# LipSync4_Main_Board_Alpha2.net
KiCad netlist of a schematic drawn in EAGLE
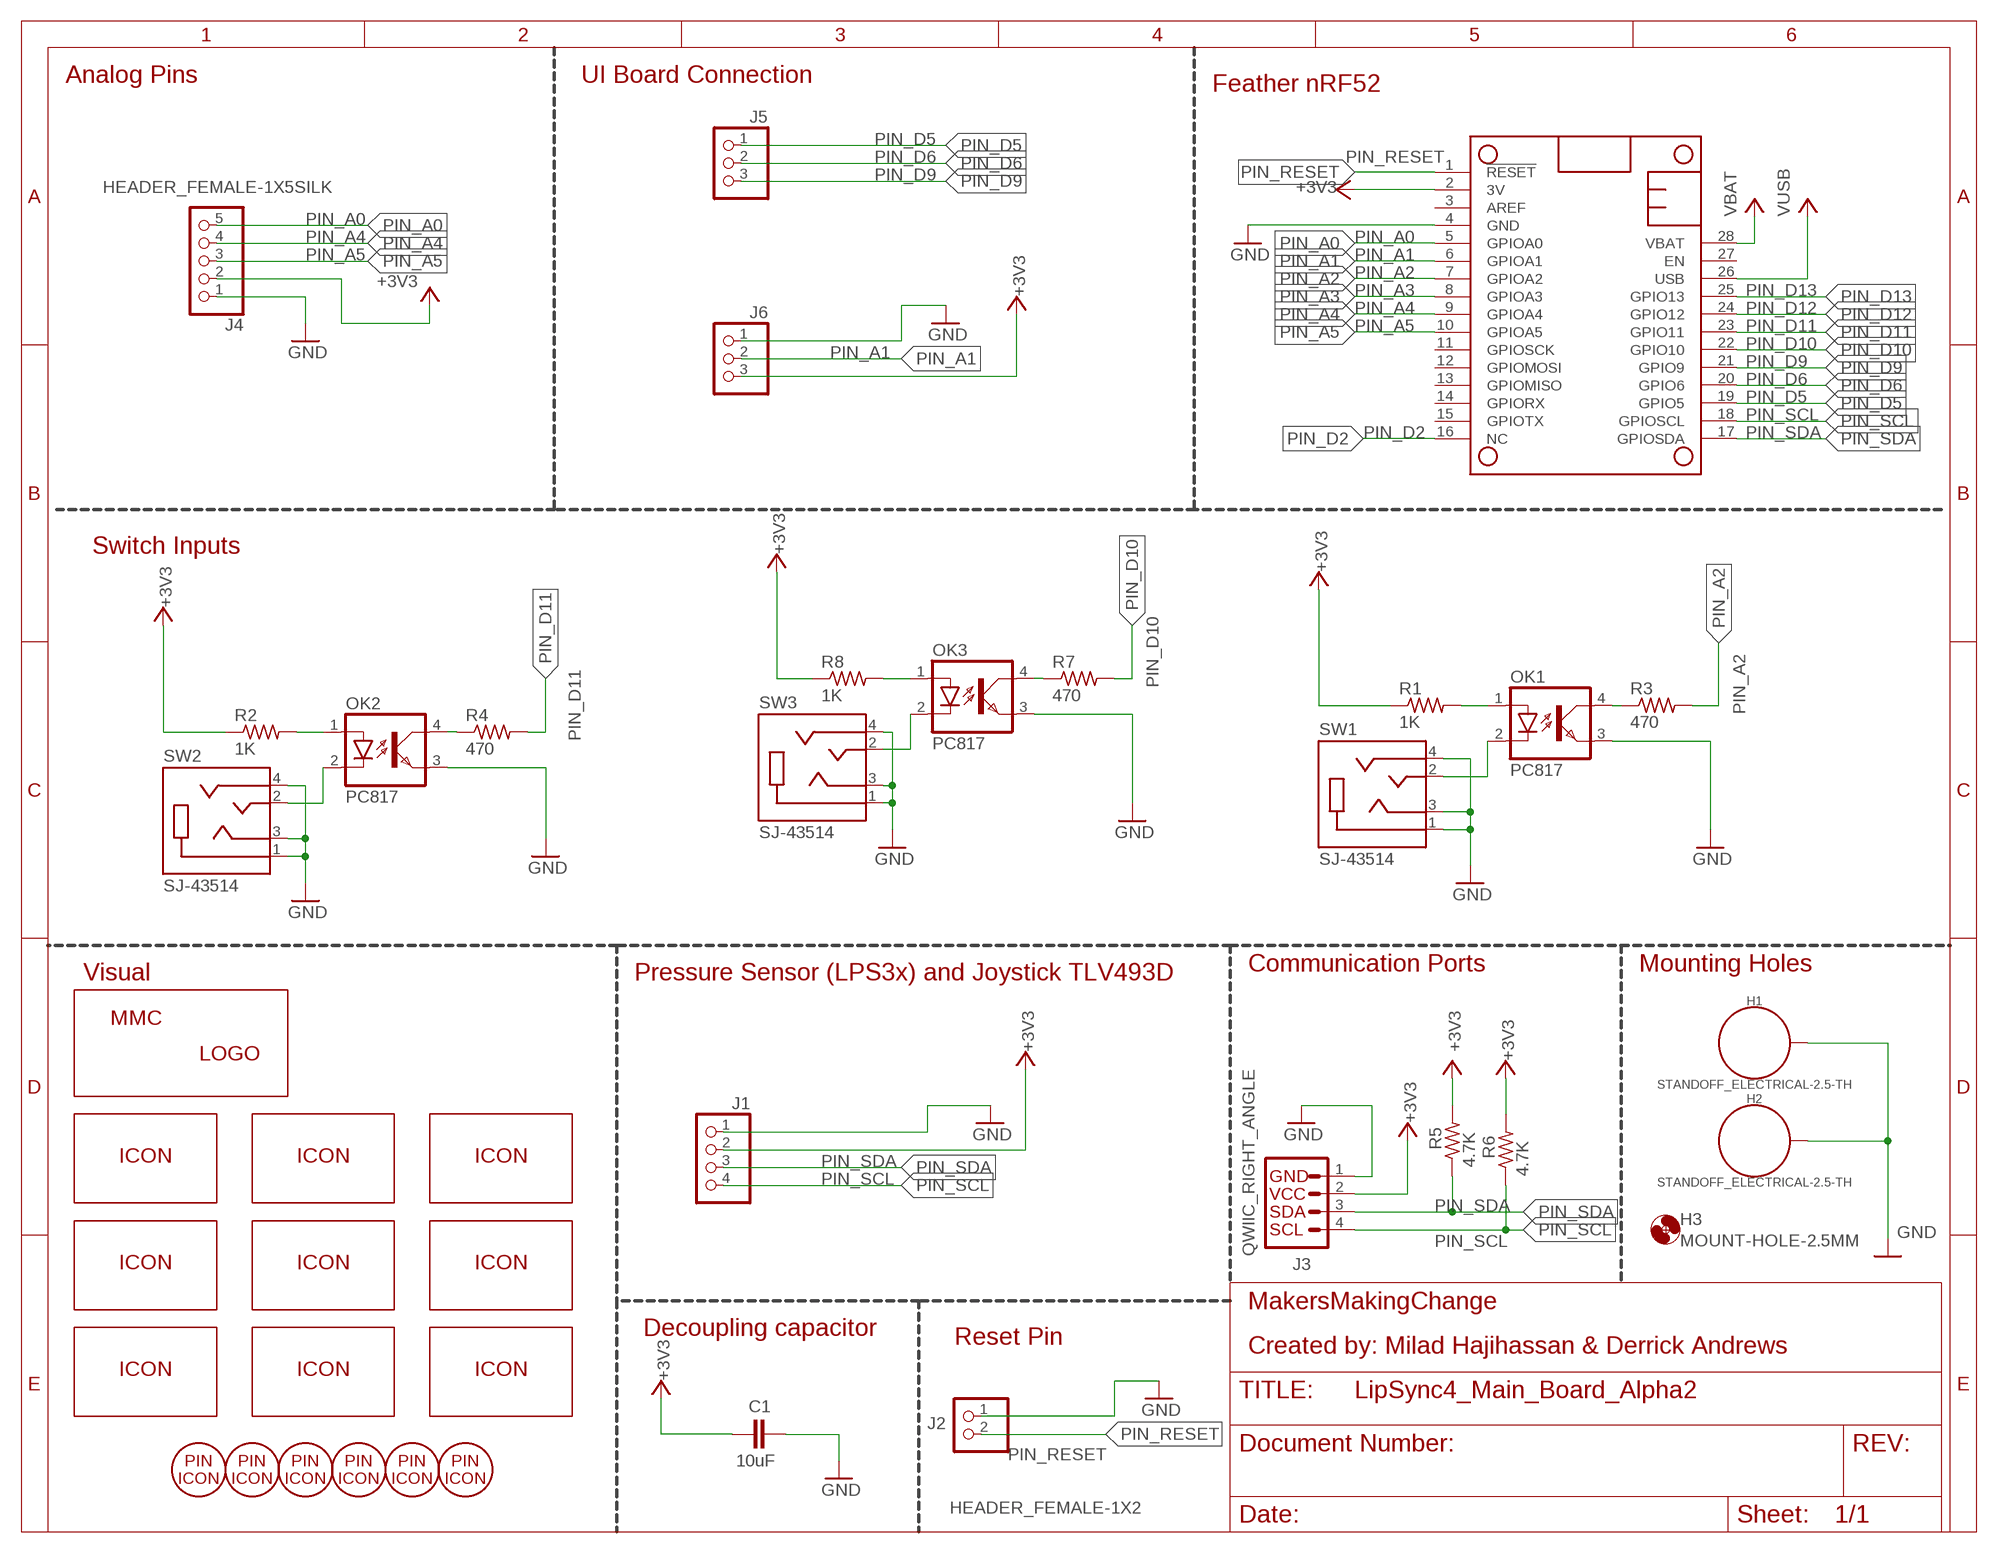
[diagram p0: schematic, sheet 1]

(export (version "E")
  (design (tool "Eeschema 10.0.6"))
  (components
    (comp (ref "C1")
      (value "10uF")
      (footprint "eagle-import:CAP-025-025X040")
      (libsource (lib "eagle-import") (part "CAPACITOR-025-025X040"))
    )
    (comp (ref "H1")
      (value "STANDOFF_ELECTRICAL-2.5-TH")
      (footprint "eagle-import:STANDOFF-ELECTRICAL-2.5-TH")
      (libsource (lib "eagle-import") (part "STANDOFF_ELECTRICAL-2.5-TH"))
    )
    (comp (ref "H2")
      (value "STANDOFF_ELECTRICAL-2.5-TH")
      (footprint "eagle-import:STANDOFF-ELECTRICAL-2.5-TH")
      (libsource (lib "eagle-import") (part "STANDOFF_ELECTRICAL-2.5-TH"))
    )
    (comp (ref "H3")
      (value "MOUNT-HOLE-2.5MM")
      (footprint "eagle-import:HOLE-2.5MM")
      (libsource (lib "eagle-import") (part "MOUNT-HOLE-2.5MM"))
    )
    (comp (ref "J1")
      (value "HEADER_FEMALE-1X4")
      (footprint "eagle-import:HEADER_FEMALE-1X04")
      (libsource (lib "eagle-import") (part "HEADER_FEMALE-1X4"))
    )
    (comp (ref "J2")
      (value "HEADER_FEMALE-1X2")
      (footprint "eagle-import:HEADER_FEMALE-1X02")
      (libsource (lib "eagle-import") (part "HEADER_FEMALE-1X2"))
    )
    (comp (ref "J3")
      (value "QWIIC_RIGHT_ANGLE")
      (footprint "eagle-import:CONNECTORS_JST04_1MM_RA")
      (libsource (lib "eagle-import") (part "QWIIC_CONNECTORSJS-1MM"))
    )
    (comp (ref "J4")
      (value "HEADER_FEMALE-1X5SILK")
      (footprint "eagle-import:HEADER_FEMALE-1X05_SILK")
      (libsource (lib "eagle-import") (part "HEADER_FEMALE-1X5SILK"))
    )
    (comp (ref "J5")
      (value "HEADER_MALE-1X03/270")
      (footprint "eagle-import:HEADER_MALE-1X03_LOCK_270")
      (libsource (lib "eagle-import") (part "HEADER_MALE-1X03/270"))
    )
    (comp (ref "J6")
      (value "HEADER_MALE-1X03/270")
      (footprint "eagle-import:HEADER_MALE-1X03_LOCK_270")
      (libsource (lib "eagle-import") (part "HEADER_MALE-1X03/270"))
    )
    (comp (ref "LABEL_ALPHA2")
      (value "MMC_ICON-ALPHA2")
      (footprint "eagle-import:ICON_ALPHA2")
      (libsource (lib "eagle-import") (part "MMC_ICON-ALPHA2"))
    )
    (comp (ref "LABEL_I2C")
      (value "MMC_ICON-I2C")
      (footprint "eagle-import:ICON_I2C")
      (libsource (lib "eagle-import") (part "MMC_ICON-I2C"))
    )
    (comp (ref "LABEL_ICON_PIN-DATA")
      (value "MMC_PIN-ICON-DATA")
      (footprint "eagle-import:PIN-ICON_DATA")
      (libsource (lib "eagle-import") (part "MMC_PIN-ICON-DATA"))
    )
    (comp (ref "LABEL_ICON_PIN-GND")
      (value "MMC_PIN-ICON-GND")
      (footprint "eagle-import:PIN-ICON_GND")
      (libsource (lib "eagle-import") (part "MMC_PIN-ICON-GND"))
    )
    (comp (ref "LABEL_ICON_PIN-VCC")
      (value "MMC_PIN-ICON-VCC")
      (footprint "eagle-import:PIN-ICON_VCC")
      (libsource (lib "eagle-import") (part "MMC_PIN-ICON-VCC"))
    )
    (comp (ref "LABEL_ICON_PIN1")
      (value "MMC_PIN-ICON-PIN1")
      (footprint "eagle-import:PIN-ICON_1")
      (libsource (lib "eagle-import") (part "MMC_PIN-ICON-PIN1"))
    )
    (comp (ref "LABEL_ICON_PIN2")
      (value "MMC_PIN-ICON-PIN2")
      (footprint "eagle-import:PIN-ICON_2")
      (libsource (lib "eagle-import") (part "MMC_PIN-ICON-PIN2"))
    )
    (comp (ref "LABEL_ICON_PIN3")
      (value "MMC_PIN-ICON-PIN3")
      (footprint "eagle-import:PIN-ICON_3")
      (libsource (lib "eagle-import") (part "MMC_PIN-ICON-PIN3"))
    )
    (comp (ref "LABEL_LIPSYNC4")
      (value "MMC_ICON-LIPSYNC4")
      (footprint "eagle-import:ICON_LIPSYNC4")
      (libsource (lib "eagle-import") (part "MMC_ICON-LIPSYNC4"))
    )
    (comp (ref "LABEL_MAIN-BOARD")
      (value "MMC_ICON-MAIN-BOARD")
      (footprint "eagle-import:ICON_MAIN-BOARD")
      (libsource (lib "eagle-import") (part "MMC_ICON-MAIN-BOARD"))
    )
    (comp (ref "LABEL_MMC")
      (value "MMC_LOGO-SM")
      (footprint "eagle-import:MMC_SMALL_LOGO")
      (libsource (lib "eagle-import") (part "MMC_LOGO-SM"))
    )
    (comp (ref "LABEL_RESET")
      (value "MMC_ICON-RESET")
      (footprint "eagle-import:ICON_RESET")
      (libsource (lib "eagle-import") (part "MMC_ICON-RESET"))
    )
    (comp (ref "LABEL_SPEAKER")
      (value "MMC_ICON-SPEAKER")
      (footprint "eagle-import:ICON_SPEAKER")
      (libsource (lib "eagle-import") (part "MMC_ICON-SPEAKER"))
    )
    (comp (ref "LABEL_STEMMA")
      (value "MMC_ICON-STEMMA")
      (footprint "eagle-import:ICON_STEMMA")
      (libsource (lib "eagle-import") (part "MMC_ICON-STEMMA"))
    )
    (comp (ref "LABE_BUTTON")
      (value "MMC_ICON-BUTTON")
      (footprint "eagle-import:ICON_BUTTON")
      (libsource (lib "eagle-import") (part "MMC_ICON-BUTTON"))
    )
    (comp (ref "LABE_LED")
      (value "MMC_ICON-LED")
      (footprint "eagle-import:ICON_LED")
      (libsource (lib "eagle-import") (part "MMC_ICON-LED"))
    )
    (comp (ref "OK1")
      (value "PC817")
      (footprint "eagle-import:DIL04")
      (libsource (lib "eagle-import") (part "PC817"))
    )
    (comp (ref "OK2")
      (value "PC817")
      (footprint "eagle-import:DIL04")
      (libsource (lib "eagle-import") (part "PC817"))
    )
    (comp (ref "OK3")
      (value "PC817")
      (footprint "eagle-import:DIL04")
      (libsource (lib "eagle-import") (part "PC817"))
    )
    (comp (ref "R1")
      (value "1K")
      (footprint "eagle-import:RESISTOR_0204_5")
      (libsource (lib "eagle-import") (part "RESISTOR-US-0204/5"))
    )
    (comp (ref "R2")
      (value "1K")
      (footprint "eagle-import:RESISTOR_0204_5")
      (libsource (lib "eagle-import") (part "RESISTOR-US-0204/5"))
    )
    (comp (ref "R3")
      (value "470")
      (footprint "eagle-import:RESISTOR_0204_5")
      (libsource (lib "eagle-import") (part "RESISTOR-US-0204/5"))
    )
    (comp (ref "R4")
      (value "470")
      (footprint "eagle-import:RESISTOR_0204_5")
      (libsource (lib "eagle-import") (part "RESISTOR-US-0204/5"))
    )
    (comp (ref "R5")
      (value "4.7K")
      (footprint "eagle-import:RESISTOR_0204_5")
      (libsource (lib "eagle-import") (part "RESISTOR-US-0204/5"))
    )
    (comp (ref "R6")
      (value "4.7K")
      (footprint "eagle-import:RESISTOR_0204_5")
      (libsource (lib "eagle-import") (part "RESISTOR-US-0204/5"))
    )
    (comp (ref "R7")
      (value "470")
      (footprint "eagle-import:RESISTOR_0204_5")
      (libsource (lib "eagle-import") (part "RESISTOR-US-0204/5"))
    )
    (comp (ref "R8")
      (value "1K")
      (footprint "eagle-import:RESISTOR_0204_5")
      (libsource (lib "eagle-import") (part "RESISTOR-US-0204/5"))
    )
    (comp (ref "SW1")
      (value "SJ-43514")
      (footprint "eagle-import:CUI_SJ-43514")
      (libsource (lib "eagle-import") (part "SJ-43514"))
    )
    (comp (ref "SW2")
      (value "SJ-43514")
      (footprint "eagle-import:CUI_SJ-43514")
      (libsource (lib "eagle-import") (part "SJ-43514"))
    )
    (comp (ref "SW3")
      (value "SJ-43514")
      (footprint "eagle-import:CUI_SJ-43514")
      (libsource (lib "eagle-import") (part "SJ-43514"))
    )
    (comp (ref "U1")
      (value "ADAFRUIT_FEATHER_NODIM")
      (footprint "eagle-import:ADAFRUIT_FEATHERWING_DIM")
      (libsource (lib "eagle-import") (part "ADAFRUIT_FEATHER_NODIM"))
    )
  )
  (nets
    (net (code "1") (name "+3V3") (class "Default")
      (node (ref "C1") (pin "2") (pinfunction "2_2") (pintype "passive"))
      (node (ref "J1") (pin "2") (pinfunction "2_2") (pintype "passive"))
      (node (ref "J3") (pin "2") (pinfunction "2_2") (pintype "power_in"))
      (node (ref "J4") (pin "2") (pinfunction "2_2") (pintype "passive"))
      (node (ref "J6") (pin "3") (pinfunction "3_3") (pintype "passive"))
      (node (ref "R1") (pin "1") (pinfunction "1_1") (pintype "passive"))
      (node (ref "R2") (pin "1") (pinfunction "1_1") (pintype "passive"))
      (node (ref "R5") (pin "2") (pinfunction "2_2") (pintype "passive"))
      (node (ref "R6") (pin "2") (pinfunction "2_2") (pintype "passive"))
      (node (ref "R8") (pin "1") (pinfunction "1_1") (pintype "passive"))
      (node (ref "U1") (pin "2") (pinfunction "3V_2") (pintype "power_in"))
    )
    (net (code "2") (name "GND") (class "Default")
      (node (ref "C1") (pin "1") (pinfunction "1_1") (pintype "passive"))
      (node (ref "H1") (pin "P1") (pinfunction "P$1_P1") (pintype "bidirectional"))
      (node (ref "H2") (pin "P1") (pinfunction "P$1_P1") (pintype "bidirectional"))
      (node (ref "J1") (pin "1") (pinfunction "1_1") (pintype "passive"))
      (node (ref "J2") (pin "1") (pinfunction "1_1") (pintype "passive"))
      (node (ref "J3") (pin "1") (pinfunction "1_1") (pintype "power_in"))
      (node (ref "J4") (pin "1") (pinfunction "1_1") (pintype "passive"))
      (node (ref "J6") (pin "1") (pinfunction "1_1") (pintype "passive"))
      (node (ref "OK1") (pin "3") (pinfunction "EMIT_3") (pintype "passive"))
      (node (ref "OK2") (pin "3") (pinfunction "EMIT_3") (pintype "passive"))
      (node (ref "OK3") (pin "3") (pinfunction "EMIT_3") (pintype "passive"))
      (node (ref "SW1") (pin "1") (pinfunction "SLEEVE_1") (pintype "passive"))
      (node (ref "SW1") (pin "3") (pinfunction "RING1_3") (pintype "passive"))
      (node (ref "SW1") (pin "4") (pinfunction "RING2_4") (pintype "passive"))
      (node (ref "SW2") (pin "1") (pinfunction "SLEEVE_1") (pintype "passive"))
      (node (ref "SW2") (pin "3") (pinfunction "RING1_3") (pintype "passive"))
      (node (ref "SW2") (pin "4") (pinfunction "RING2_4") (pintype "passive"))
      (node (ref "SW3") (pin "1") (pinfunction "SLEEVE_1") (pintype "passive"))
      (node (ref "SW3") (pin "3") (pinfunction "RING1_3") (pintype "passive"))
      (node (ref "SW3") (pin "4") (pinfunction "RING2_4") (pintype "passive"))
      (node (ref "U1") (pin "4") (pinfunction "GND_4") (pintype "power_in"))
    )
    (net (code "3") (name "Net-(OK1-A)") (class "Default")
      (node (ref "OK1") (pin "1") (pinfunction "A_1") (pintype "passive"))
      (node (ref "R1") (pin "2") (pinfunction "2_2") (pintype "passive"))
    )
    (net (code "4") (name "Net-(OK1-C)") (class "Default")
      (node (ref "OK1") (pin "2") (pinfunction "C_2") (pintype "passive"))
      (node (ref "SW1") (pin "2") (pinfunction "TIP_2") (pintype "passive"))
    )
    (net (code "5") (name "Net-(OK1-COL)") (class "Default")
      (node (ref "OK1") (pin "4") (pinfunction "COL_4") (pintype "passive"))
      (node (ref "R3") (pin "1") (pinfunction "1_1") (pintype "passive"))
    )
    (net (code "6") (name "Net-(OK2-A)") (class "Default")
      (node (ref "OK2") (pin "1") (pinfunction "A_1") (pintype "passive"))
      (node (ref "R2") (pin "2") (pinfunction "2_2") (pintype "passive"))
    )
    (net (code "7") (name "Net-(OK2-C)") (class "Default")
      (node (ref "OK2") (pin "2") (pinfunction "C_2") (pintype "passive"))
      (node (ref "SW2") (pin "2") (pinfunction "TIP_2") (pintype "passive"))
    )
    (net (code "8") (name "Net-(OK2-COL)") (class "Default")
      (node (ref "OK2") (pin "4") (pinfunction "COL_4") (pintype "passive"))
      (node (ref "R4") (pin "1") (pinfunction "1_1") (pintype "passive"))
    )
    (net (code "9") (name "Net-(OK3-A)") (class "Default")
      (node (ref "OK3") (pin "1") (pinfunction "A_1") (pintype "passive"))
      (node (ref "R8") (pin "2") (pinfunction "2_2") (pintype "passive"))
    )
    (net (code "10") (name "Net-(OK3-C)") (class "Default")
      (node (ref "OK3") (pin "2") (pinfunction "C_2") (pintype "passive"))
      (node (ref "SW3") (pin "2") (pinfunction "TIP_2") (pintype "passive"))
    )
    (net (code "11") (name "Net-(OK3-COL)") (class "Default")
      (node (ref "OK3") (pin "4") (pinfunction "COL_4") (pintype "passive"))
      (node (ref "R7") (pin "1") (pinfunction "1_1") (pintype "passive"))
    )
    (net (code "12") (name "PIN_A0") (class "Default")
      (node (ref "J4") (pin "5") (pinfunction "5_5") (pintype "passive"))
      (node (ref "U1") (pin "5") (pinfunction "GPIOA0_5") (pintype "bidirectional"))
    )
    (net (code "13") (name "PIN_A1") (class "Default")
      (node (ref "J6") (pin "2") (pinfunction "2_2") (pintype "passive"))
      (node (ref "U1") (pin "6") (pinfunction "GPIOA1_6") (pintype "bidirectional"))
    )
    (net (code "14") (name "PIN_A2") (class "Default")
      (node (ref "R3") (pin "2") (pinfunction "2_2") (pintype "passive"))
      (node (ref "U1") (pin "7") (pinfunction "GPIOA2_7") (pintype "bidirectional"))
    )
    (net (code "15") (name "PIN_A3") (class "Default")
      (node (ref "U1") (pin "8") (pinfunction "GPIOA3_8") (pintype "bidirectional"))
    )
    (net (code "16") (name "PIN_A4") (class "Default")
      (node (ref "J4") (pin "4") (pinfunction "4_4") (pintype "passive"))
      (node (ref "U1") (pin "9") (pinfunction "GPIOA4_9") (pintype "bidirectional"))
    )
    (net (code "17") (name "PIN_A5") (class "Default")
      (node (ref "J4") (pin "3") (pinfunction "3_3") (pintype "passive"))
      (node (ref "U1") (pin "10") (pinfunction "GPIOA5_10") (pintype "bidirectional"))
    )
    (net (code "18") (name "PIN_D2") (class "Default")
      (node (ref "U1") (pin "16") (pinfunction "NC_16") (pintype "passive"))
    )
    (net (code "19") (name "PIN_D5") (class "Default")
      (node (ref "J5") (pin "1") (pinfunction "1_1") (pintype "passive"))
      (node (ref "U1") (pin "19") (pinfunction "GPIO5_19") (pintype "bidirectional"))
    )
    (net (code "20") (name "PIN_D6") (class "Default")
      (node (ref "J5") (pin "2") (pinfunction "2_2") (pintype "passive"))
      (node (ref "U1") (pin "20") (pinfunction "GPIO6_20") (pintype "bidirectional"))
    )
    (net (code "21") (name "PIN_D9") (class "Default")
      (node (ref "J5") (pin "3") (pinfunction "3_3") (pintype "passive"))
      (node (ref "U1") (pin "21") (pinfunction "GPIO9_21") (pintype "bidirectional"))
    )
    (net (code "22") (name "PIN_D10") (class "Default")
      (node (ref "R7") (pin "2") (pinfunction "2_2") (pintype "passive"))
      (node (ref "U1") (pin "22") (pinfunction "GPIO10_22") (pintype "bidirectional"))
    )
    (net (code "23") (name "PIN_D11") (class "Default")
      (node (ref "R4") (pin "2") (pinfunction "2_2") (pintype "passive"))
      (node (ref "U1") (pin "23") (pinfunction "GPIO11_23") (pintype "bidirectional"))
    )
    (net (code "24") (name "PIN_D12") (class "Default")
      (node (ref "U1") (pin "24") (pinfunction "GPIO12_24") (pintype "bidirectional"))
    )
    (net (code "25") (name "PIN_D13") (class "Default")
      (node (ref "U1") (pin "25") (pinfunction "GPIO13_25") (pintype "bidirectional"))
    )
    (net (code "26") (name "PIN_RESET") (class "Default")
      (node (ref "J2") (pin "2") (pinfunction "2_2") (pintype "passive"))
      (node (ref "U1") (pin "1") (pinfunction "~{RESET}_1") (pintype "input"))
    )
    (net (code "27") (name "PIN_SCL") (class "Default")
      (node (ref "J1") (pin "4") (pinfunction "4_4") (pintype "passive"))
      (node (ref "J3") (pin "4") (pinfunction "4_4") (pintype "passive"))
      (node (ref "R6") (pin "1") (pinfunction "1_1") (pintype "passive"))
      (node (ref "U1") (pin "18") (pinfunction "GPIOSCL_18") (pintype "bidirectional"))
    )
    (net (code "28") (name "PIN_SDA") (class "Default")
      (node (ref "J1") (pin "3") (pinfunction "3_3") (pintype "passive"))
      (node (ref "J3") (pin "3") (pinfunction "3_3") (pintype "passive"))
      (node (ref "R5") (pin "1") (pinfunction "1_1") (pintype "passive"))
      (node (ref "U1") (pin "17") (pinfunction "GPIOSDA_17") (pintype "bidirectional"))
    )
    (net (code "29") (name "VBAT") (class "Default")
      (node (ref "U1") (pin "28") (pinfunction "VBAT_28") (pintype "power_in"))
    )
    (net (code "30") (name "VUSB") (class "Default")
      (node (ref "U1") (pin "26") (pinfunction "USB_26") (pintype "power_in"))
    )
    (net (code "31") (name "unconnected-(U1-AREF-Pad3)") (class "Default")
      (node (ref "U1") (pin "3") (pinfunction "AREF_3") (pintype "passive"))
    )
    (net (code "32") (name "unconnected-(U1-EN-Pad27)") (class "Default")
      (node (ref "U1") (pin "27") (pinfunction "EN_27") (pintype "passive"))
    )
    (net (code "33") (name "unconnected-(U1-GPIOMISO-Pad13)") (class "Default")
      (node (ref "U1") (pin "13") (pinfunction "GPIOMISO_13") (pintype "bidirectional"))
    )
    (net (code "34") (name "unconnected-(U1-GPIOMOSI-Pad12)") (class "Default")
      (node (ref "U1") (pin "12") (pinfunction "GPIOMOSI_12") (pintype "bidirectional"))
    )
    (net (code "35") (name "unconnected-(U1-GPIORX-Pad14)") (class "Default")
      (node (ref "U1") (pin "14") (pinfunction "GPIORX_14") (pintype "bidirectional"))
    )
    (net (code "36") (name "unconnected-(U1-GPIOSCK-Pad11)") (class "Default")
      (node (ref "U1") (pin "11") (pinfunction "GPIOSCK_11") (pintype "bidirectional"))
    )
    (net (code "37") (name "unconnected-(U1-GPIOTX-Pad15)") (class "Default")
      (node (ref "U1") (pin "15") (pinfunction "GPIOTX_15") (pintype "bidirectional"))
    )
  )
)
